# untitled.net
KiCad netlist of a schematic drawn in EAGLE
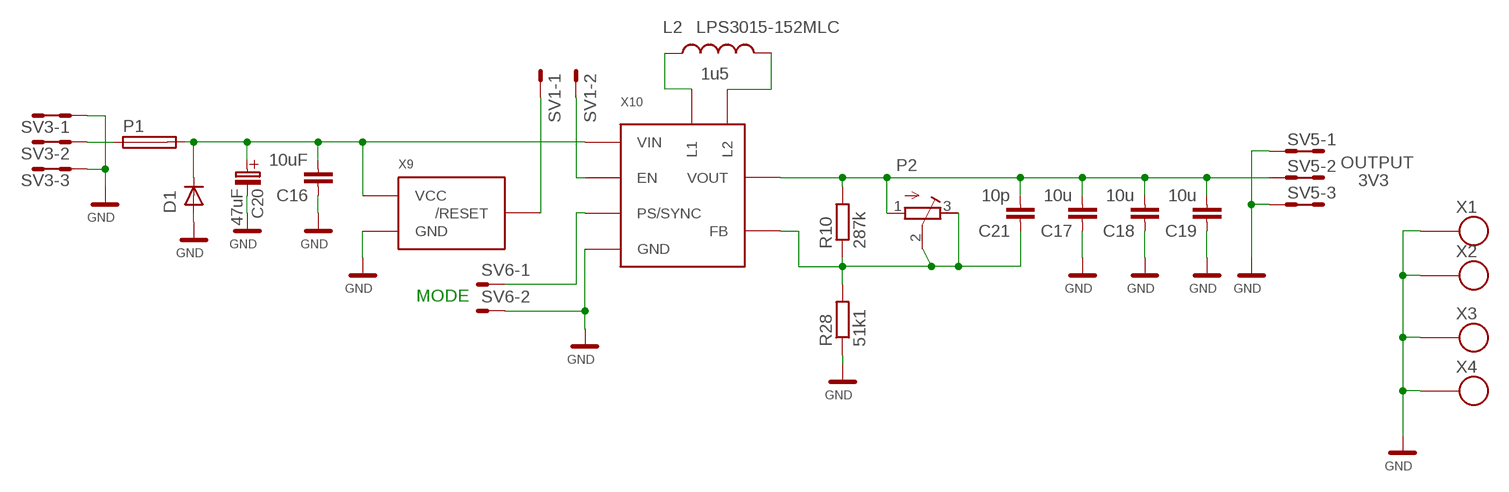
[diagram p0: schematic, sheet 1]

(export (version "E")
  (design (tool "Eeschema 10.0.6"))
  (components
    (comp (ref "C16")
      (value "10uF")
      (footprint "eagle-import:C0805")
      (libsource (lib "eagle-import") (part "C0805"))
    )
    (comp (ref "C17")
      (value "10u")
      (footprint "eagle-import:C0805")
      (libsource (lib "eagle-import") (part "C0805"))
    )
    (comp (ref "C18")
      (value "10u")
      (footprint "eagle-import:C0805")
      (libsource (lib "eagle-import") (part "C0805"))
    )
    (comp (ref "C19")
      (value "10u")
      (footprint "eagle-import:C0805")
      (libsource (lib "eagle-import") (part "C0805"))
    )
    (comp (ref "C20") (value "47uF") (footprint "eagle-import:B") (libsource (lib "eagle-import") (part "B")))
    (comp (ref "C21")
      (value "10p")
      (footprint "eagle-import:0603")
      (libsource (lib "eagle-import") (part "C0603"))
    )
    (comp (ref "D1")
      (value "D-OB.SMA")
      (footprint "eagle-import:SMA")
      (libsource (lib "eagle-import") (part "D-OB.SMA"))
    )
    (comp (ref "L2")
      (value "LPS3015-152MLC")
      (footprint "eagle-import:LPS3015")
      (libsource (lib "eagle-import") (part "LPS3015"))
    )
    (comp (ref "P1")
      (value "POJISTKA_1812")
      (footprint "eagle-import:1812")
      (libsource (lib "eagle-import") (part "POJISTKA_1812"))
    )
    (comp (ref "P2")
      (value "TRIM_CA9MTV10")
      (footprint "eagle-import:TRIM_CA9MTV10")
      (libsource (lib "eagle-import") (part "TRIM_CA9MTV10"))
    )
    (comp (ref "R10")
      (value "287k")
      (footprint "eagle-import:0603")
      (libsource (lib "eagle-import") (part "R0603"))
    )
    (comp (ref "R28")
      (value "51k1")
      (footprint "eagle-import:0603")
      (libsource (lib "eagle-import") (part "R0603"))
    )
    (comp (ref "SV1")
      (value "MA02-1")
      (footprint "eagle-import:MA02-1")
      (libsource (lib "eagle-import") (part "MA02-1"))
    )
    (comp (ref "SV3")
      (value "MA03-2")
      (footprint "eagle-import:MA03-2")
      (libsource (lib "eagle-import") (part "MA03-2"))
    )
    (comp (ref "SV5")
      (value "MA03-2")
      (footprint "eagle-import:MA03-2")
      (libsource (lib "eagle-import") (part "MA03-2"))
    )
    (comp (ref "SV6")
      (value "MA02-1")
      (footprint "eagle-import:MA02-1")
      (libsource (lib "eagle-import") (part "MA02-1"))
    )
    (comp (ref "X1")
      (value "SROUB3M")
      (footprint "eagle-import:SROUB3M")
      (libsource (lib "eagle-import") (part "SROUB3M"))
    )
    (comp (ref "X2")
      (value "SROUB3M")
      (footprint "eagle-import:SROUB3M")
      (libsource (lib "eagle-import") (part "SROUB3M"))
    )
    (comp (ref "X3")
      (value "SROUB3M")
      (footprint "eagle-import:SROUB3M")
      (libsource (lib "eagle-import") (part "SROUB3M"))
    )
    (comp (ref "X4")
      (value "SROUB3M")
      (footprint "eagle-import:SROUB3M")
      (libsource (lib "eagle-import") (part "SROUB3M"))
    )
    (comp (ref "X9")
      (value "APX809-26SA")
      (footprint "eagle-import:SOT23")
      (libsource (lib "eagle-import") (part "APX809-26SA"))
    )
    (comp (ref "X10")
      (value "TPS63036")
      (footprint "eagle-import:DSBGA8")
      (libsource (lib "eagle-import") (part "TPS63036"))
    )
  )
  (nets
    (net (code "1") (name "GND") (class "Default")
      (node (ref "C16") (pin "1") (pinfunction "1_1") (pintype "passive"))
      (node (ref "C17") (pin "1") (pinfunction "1_1") (pintype "passive"))
      (node (ref "C18") (pin "1") (pinfunction "1_1") (pintype "passive"))
      (node (ref "C19") (pin "1") (pinfunction "1_1") (pintype "passive"))
      (node (ref "C20") (pin "-") (pinfunction "C_EL-_-") (pintype "passive"))
      (node (ref "D1") (pin "A") (pinfunction "A_A") (pintype "passive"))
      (node (ref "R28") (pin "1") (pinfunction "1_1") (pintype "passive"))
      (node (ref "SV3") (pin "1") (pinfunction "K_1") (pintype "passive"))
      (node (ref "SV3") (pin "2") (pinfunction "K_2") (pintype "passive"))
      (node (ref "SV3") (pin "5") (pinfunction "K_5") (pintype "passive"))
      (node (ref "SV3") (pin "6") (pinfunction "K_6") (pintype "passive"))
      (node (ref "SV5") (pin "1") (pinfunction "K_1") (pintype "passive"))
      (node (ref "SV5") (pin "2") (pinfunction "K_2") (pintype "passive"))
      (node (ref "SV5") (pin "5") (pinfunction "K_5") (pintype "passive"))
      (node (ref "SV5") (pin "6") (pinfunction "K_6") (pintype "passive"))
      (node (ref "SV6") (pin "2") (pinfunction "P$1_2") (pintype "passive"))
      (node (ref "X1") (pin "P$1") (pinfunction "P$1_P$1") (pintype "bidirectional"))
      (node (ref "X10") (pin "C2") (pinfunction "GND_C2") (pintype "passive"))
      (node (ref "X2") (pin "P$1") (pinfunction "P$1_P$1") (pintype "bidirectional"))
      (node (ref "X3") (pin "P$1") (pinfunction "P$1_P$1") (pintype "bidirectional"))
      (node (ref "X4") (pin "P$1") (pinfunction "P$1_P$1") (pintype "bidirectional"))
      (node (ref "X9") (pin "1") (pinfunction "GND_1") (pintype "passive"))
    )
    (net (code "2") (name "Net-(C20-C_EL+)") (class "Default")
      (node (ref "C16") (pin "2") (pinfunction "2_2") (pintype "passive"))
      (node (ref "C20") (pin "+") (pinfunction "C_EL+_+") (pintype "passive"))
      (node (ref "D1") (pin "K") (pinfunction "C_K") (pintype "passive"))
      (node (ref "P1") (pin "2") (pinfunction "2_2") (pintype "passive"))
      (node (ref "X10") (pin "A1") (pinfunction "VIN_A1") (pintype "input"))
      (node (ref "X9") (pin "3") (pinfunction "VCC_3") (pintype "input"))
    )
    (net (code "3") (name "Net-(P1-Pad1)") (class "Default")
      (node (ref "P1") (pin "1") (pinfunction "1_1") (pintype "passive"))
      (node (ref "SV3") (pin "3") (pinfunction "K_3") (pintype "passive"))
      (node (ref "SV3") (pin "4") (pinfunction "K_4") (pintype "passive"))
    )
    (net (code "4") (name "Net-(SV1A-P$1)") (class "Default")
      (node (ref "SV1") (pin "1") (pinfunction "P$1_1") (pintype "passive"))
      (node (ref "X9") (pin "2") (pinfunction "/RESET_2") (pintype "passive"))
    )
    (net (code "5") (name "Net-(SV1B-P$1)") (class "Default")
      (node (ref "SV1") (pin "2") (pinfunction "P$1_2") (pintype "passive"))
      (node (ref "X10") (pin "A2") (pinfunction "EN_A2") (pintype "input"))
    )
    (net (code "6") (name "Net-(SV6A-P$1)") (class "Default")
      (node (ref "SV6") (pin "1") (pinfunction "P$1_1") (pintype "passive"))
      (node (ref "X10") (pin "B2") (pinfunction "PS/SYNC_B2") (pintype "input"))
    )
    (net (code "7") (name "Net-(X10-FB)") (class "Default")
      (node (ref "C21") (pin "1") (pinfunction "1_1") (pintype "passive"))
      (node (ref "P2") (pin "2") (pinfunction "2_2") (pintype "passive"))
      (node (ref "P2") (pin "3") (pinfunction "3_3") (pintype "passive"))
      (node (ref "R10") (pin "1") (pinfunction "1_1") (pintype "passive"))
      (node (ref "R28") (pin "2") (pinfunction "2_2") (pintype "passive"))
      (node (ref "X10") (pin "D2") (pinfunction "FB_D2") (pintype "input"))
    )
    (net (code "8") (name "Net-(X10-L1)") (class "Default")
      (node (ref "L2") (pin "1-1") (pinfunction "1_1-1") (pintype "passive"))
      (node (ref "L2") (pin "1-2") (pinfunction "1_1-2") (pintype "passive"))
      (node (ref "L2") (pin "1-3") (pinfunction "1_1-3") (pintype "passive"))
      (node (ref "X10") (pin "B1") (pinfunction "L1_B1") (pintype "passive"))
    )
    (net (code "9") (name "Net-(X10-L2)") (class "Default")
      (node (ref "L2") (pin "2-1") (pinfunction "2_2-1") (pintype "passive"))
      (node (ref "L2") (pin "2-2") (pinfunction "2_2-2") (pintype "passive"))
      (node (ref "L2") (pin "2-3") (pinfunction "2_2-3") (pintype "passive"))
      (node (ref "X10") (pin "C1") (pinfunction "L2_C1") (pintype "passive"))
    )
    (net (code "10") (name "Net-(X10-VOUT)") (class "Default")
      (node (ref "C17") (pin "2") (pinfunction "2_2") (pintype "passive"))
      (node (ref "C18") (pin "2") (pinfunction "2_2") (pintype "passive"))
      (node (ref "C19") (pin "2") (pinfunction "2_2") (pintype "passive"))
      (node (ref "C21") (pin "2") (pinfunction "2_2") (pintype "passive"))
      (node (ref "P2") (pin "1") (pinfunction "1_1") (pintype "passive"))
      (node (ref "R10") (pin "2") (pinfunction "2_2") (pintype "passive"))
      (node (ref "SV5") (pin "3") (pinfunction "K_3") (pintype "passive"))
      (node (ref "SV5") (pin "4") (pinfunction "K_4") (pintype "passive"))
      (node (ref "X10") (pin "D1") (pinfunction "VOUT_D1") (pintype "output"))
    )
  )
)
